# LED-DRIVER.net
KiCad netlist of a schematic drawn in Altium Designer
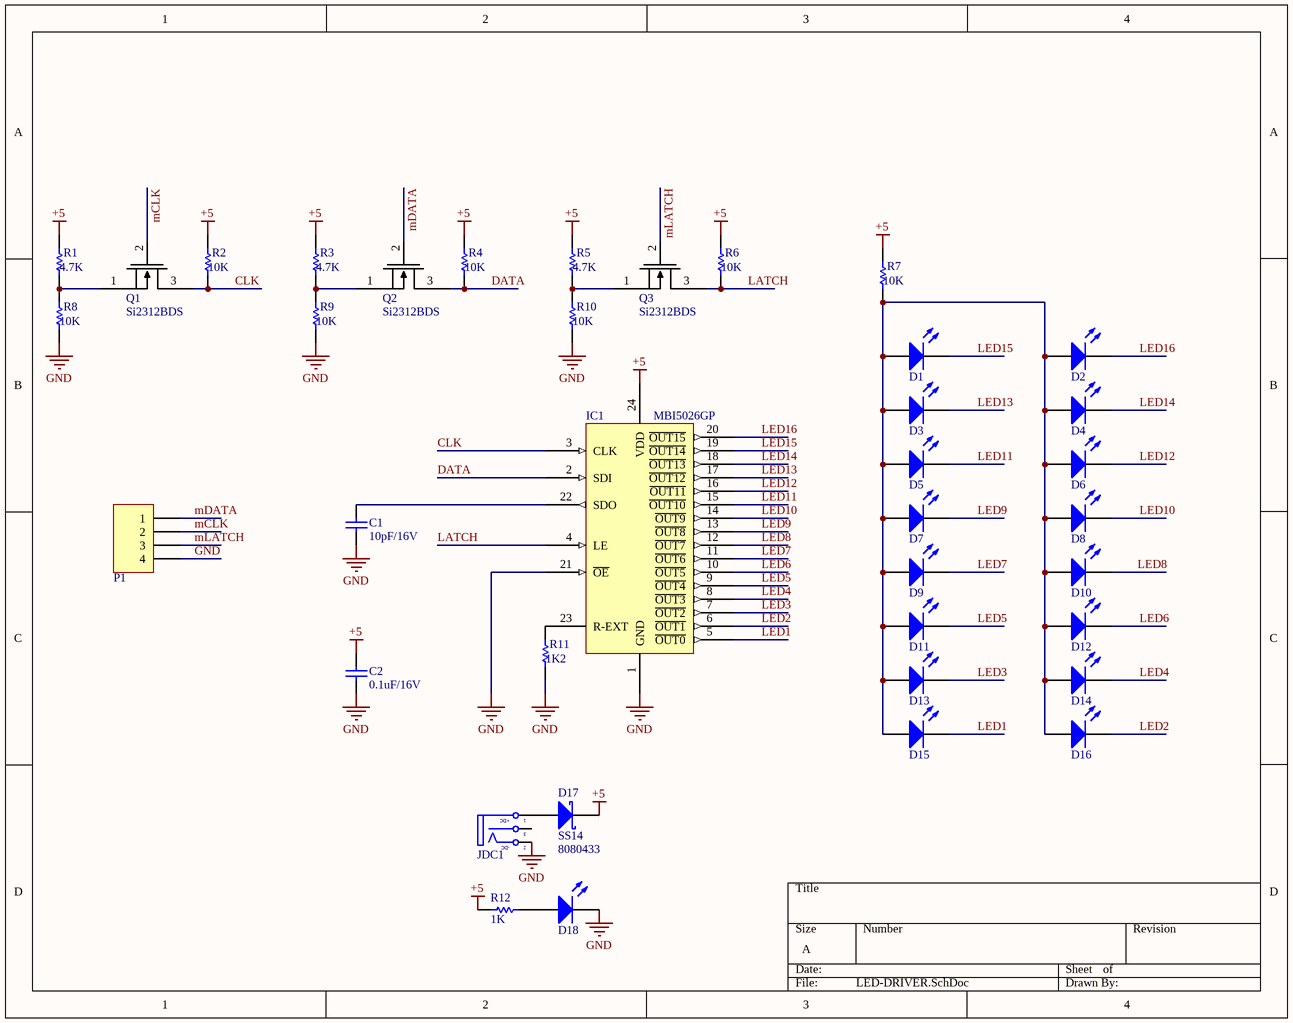
[diagram p0: LED-DRIVER.SchDoc]

(export (version "E")
  (design (tool "Eeschema 10.0.6"))
  (components
    (comp (ref "C1")
      (value "10pF/16V")
      (footprint "CAP-SM-0603")
      (description "Capacitor")
      (fields (field (name "Comment") "Cap Non-Pol SMD"))
      (libsource (lib "PIF_Library") (part "Cap Non-Pol SMD"))
    )
    (comp (ref "C2")
      (value "0.1uF/16V")
      (footprint "CAP-SM-0603")
      (description "Capacitor")
      (fields (field (name "Comment") "Cap Non-Pol SMD"))
      (libsource (lib "PIF_Library") (part "Cap Non-Pol SMD"))
    )
    (comp (ref "D1")
      (value "LED SMD")
      (footprint "LED_0603_Blue")
      (description "LED")
      (libsource (lib "PIF_Library") (part "LED SMD"))
    )
    (comp (ref "D2")
      (value "LED SMD")
      (footprint "LED_0603_Blue")
      (description "LED")
      (libsource (lib "PIF_Library") (part "LED SMD"))
    )
    (comp (ref "D3")
      (value "LED SMD")
      (footprint "LED_0603_Blue")
      (description "LED")
      (libsource (lib "PIF_Library") (part "LED SMD"))
    )
    (comp (ref "D4")
      (value "LED SMD")
      (footprint "LED_0603_Blue")
      (description "LED")
      (libsource (lib "PIF_Library") (part "LED SMD"))
    )
    (comp (ref "D5")
      (value "LED SMD")
      (footprint "LED_0603_Blue")
      (description "LED")
      (libsource (lib "PIF_Library") (part "LED SMD"))
    )
    (comp (ref "D6")
      (value "LED SMD")
      (footprint "LED_0603_Blue")
      (description "LED")
      (libsource (lib "PIF_Library") (part "LED SMD"))
    )
    (comp (ref "D7")
      (value "LED SMD")
      (footprint "LED_0603_Blue")
      (description "LED")
      (libsource (lib "PIF_Library") (part "LED SMD"))
    )
    (comp (ref "D8")
      (value "LED SMD")
      (footprint "LED_0603_Blue")
      (description "LED")
      (libsource (lib "PIF_Library") (part "LED SMD"))
    )
    (comp (ref "D9")
      (value "LED SMD")
      (footprint "LED_0603_Blue")
      (description "LED")
      (libsource (lib "PIF_Library") (part "LED SMD"))
    )
    (comp (ref "D10")
      (value "LED SMD")
      (footprint "LED_0603_Blue")
      (description "LED")
      (libsource (lib "PIF_Library") (part "LED SMD"))
    )
    (comp (ref "D11")
      (value "LED SMD")
      (footprint "LED_0603_Blue")
      (description "LED")
      (libsource (lib "PIF_Library") (part "LED SMD"))
    )
    (comp (ref "D12")
      (value "LED SMD")
      (footprint "LED_0603_Blue")
      (description "LED")
      (libsource (lib "PIF_Library") (part "LED SMD"))
    )
    (comp (ref "D13")
      (value "LED SMD")
      (footprint "LED_0603_Blue")
      (description "LED")
      (libsource (lib "PIF_Library") (part "LED SMD"))
    )
    (comp (ref "D14")
      (value "LED SMD")
      (footprint "LED_0603_Blue")
      (description "LED")
      (libsource (lib "PIF_Library") (part "LED SMD"))
    )
    (comp (ref "D15")
      (value "LED SMD")
      (footprint "LED_0603_Blue")
      (description "LED")
      (libsource (lib "PIF_Library") (part "LED SMD"))
    )
    (comp (ref "D16")
      (value "LED SMD")
      (footprint "LED_0603_Blue")
      (description "LED")
      (libsource (lib "PIF_Library") (part "LED SMD"))
    )
    (comp (ref "D17")
      (value "D Schottky")
      (footprint "SS34")
      (description "Schottky Diode")
      (fields
        (field (name "SUPPLIER PART NUMBER 1") "SS14")
        (field (name "SUPPLIER PART NUMBER 2") "8080433")
        (field (name "PUBLISHER") "Altium Limited")
      )
      (libsource (lib "PIF_Library") (part "D Schottky"))
    )
    (comp (ref "D18")
      (value "LED SMD")
      (footprint "LED_0603_Blue")
      (description "LED")
      (libsource (lib "PIF_Library") (part "LED SMD"))
    )
    (comp (ref "IC1")
      (value "MBI5026GP")
      (footprint "MBI5026GP")
      (description "16-bit Constant Current LED Sink Driver")
      (libsource (lib "Giang's Libs") (part "MBI5026GP"))
    )
    (comp (ref "JDC1")
      (value "Jack DC")
      (footprint "DC-IN")
      (description "Jack DC input")
      (libsource (lib "PIF_Library") (part "Jack DC"))
    )
    (comp (ref "P1")
      (value "Header 4")
      (footprint "JP4")
      (description "Header, 4-Pin")
      (fields (field (name "PUBLISHER") "Altium Limited"))
      (libsource (lib "PIF_Library") (part "Header 4"))
    )
    (comp (ref "Q1")
      (value "Si2312BDS")
      (footprint "SOT95P245X110-3N")
      (fields (field (name "MANUFACTURER") "Vishay Semiconductors"))
      (libsource (lib "MiclsLib") (part "Si2312BDS"))
    )
    (comp (ref "Q2")
      (value "Si2312BDS")
      (footprint "SOT95P245X110-3N")
      (fields (field (name "MANUFACTURER") "Vishay Semiconductors"))
      (libsource (lib "MiclsLib") (part "Si2312BDS"))
    )
    (comp (ref "Q3")
      (value "Si2312BDS")
      (footprint "SOT95P245X110-3N")
      (fields (field (name "MANUFACTURER") "Vishay Semiconductors"))
      (libsource (lib "MiclsLib") (part "Si2312BDS"))
    )
    (comp (ref "R1")
      (value "4.7K")
      (footprint "RES-SM-0603")
      (description "Resistor")
      (fields (field (name "Comment") "RESISTOR SMD"))
      (libsource (lib "PIF_Library") (part "RESISTOR SMD"))
    )
    (comp (ref "R2")
      (value "10K")
      (footprint "RES-SM-0603")
      (description "Resistor")
      (fields (field (name "Comment") "RESISTOR SMD"))
      (libsource (lib "PIF_Library") (part "RESISTOR SMD"))
    )
    (comp (ref "R3")
      (value "4.7K")
      (footprint "RES-SM-0603")
      (description "Resistor")
      (fields (field (name "Comment") "RESISTOR SMD"))
      (libsource (lib "PIF_Library") (part "RESISTOR SMD"))
    )
    (comp (ref "R4")
      (value "10K")
      (footprint "RES-SM-0603")
      (description "Resistor")
      (fields (field (name "Comment") "RESISTOR SMD"))
      (libsource (lib "PIF_Library") (part "RESISTOR SMD"))
    )
    (comp (ref "R5")
      (value "4.7K")
      (footprint "RES-SM-0603")
      (description "Resistor")
      (fields (field (name "Comment") "RESISTOR SMD"))
      (libsource (lib "PIF_Library") (part "RESISTOR SMD"))
    )
    (comp (ref "R6")
      (value "10K")
      (footprint "RES-SM-0603")
      (description "Resistor")
      (fields (field (name "Comment") "RESISTOR SMD"))
      (libsource (lib "PIF_Library") (part "RESISTOR SMD"))
    )
    (comp (ref "R7")
      (value "10K")
      (footprint "RES-SM-0603")
      (description "Resistor")
      (fields (field (name "Comment") "RESISTOR SMD"))
      (libsource (lib "PIF_Library") (part "RESISTOR SMD"))
    )
    (comp (ref "R8")
      (value "10K")
      (footprint "RES-SM-0603")
      (description "Resistor")
      (fields (field (name "Comment") "RESISTOR SMD"))
      (libsource (lib "PIF_Library") (part "RESISTOR SMD"))
    )
    (comp (ref "R9")
      (value "10K")
      (footprint "RES-SM-0603")
      (description "Resistor")
      (fields (field (name "Comment") "RESISTOR SMD"))
      (libsource (lib "PIF_Library") (part "RESISTOR SMD"))
    )
    (comp (ref "R10")
      (value "10K")
      (footprint "RES-SM-0603")
      (description "Resistor")
      (fields (field (name "Comment") "RESISTOR SMD"))
      (libsource (lib "PIF_Library") (part "RESISTOR SMD"))
    )
    (comp (ref "R11")
      (value "1K2")
      (footprint "RES-SM-0603")
      (description "Resistor")
      (fields (field (name "Comment") "RESISTOR SMD"))
      (libsource (lib "PIF_Library") (part "RESISTOR SMD"))
    )
    (comp (ref "R12")
      (value "1K")
      (footprint "RES-SM-0603")
      (description "Resistor")
      (fields (field (name "Comment") "RESISTOR SMD"))
      (libsource (lib "PIF_Library") (part "RESISTOR SMD"))
    )
  )
  (nets
    (net (code "1") (name "+5") (class "Default")
      (node (ref "C2") (pin "2") (pinfunction "2_2") (pintype "passive"))
      (node (ref "D17") (pin "K") (pinfunction "K_K") (pintype "passive"))
      (node (ref "IC1") (pin "24") (pinfunction "VDD_24") (pintype "power_in"))
      (node (ref "R1") (pin "2") (pinfunction "2_2") (pintype "passive"))
      (node (ref "R12") (pin "1") (pinfunction "1_1") (pintype "passive"))
      (node (ref "R2") (pin "2") (pinfunction "2_2") (pintype "passive"))
      (node (ref "R3") (pin "2") (pinfunction "2_2") (pintype "passive"))
      (node (ref "R4") (pin "2") (pinfunction "2_2") (pintype "passive"))
      (node (ref "R5") (pin "2") (pinfunction "2_2") (pintype "passive"))
      (node (ref "R6") (pin "2") (pinfunction "2_2") (pintype "passive"))
      (node (ref "R7") (pin "2") (pinfunction "2_2") (pintype "passive"))
    )
    (net (code "2") (name "/CLK") (class "Default")
      (node (ref "IC1") (pin "3") (pinfunction "CLK_3") (pintype "input"))
      (node (ref "Q1") (pin "3") (pinfunction "3_3") (pintype "passive"))
      (node (ref "R2") (pin "1") (pinfunction "1_1") (pintype "passive"))
    )
    (net (code "3") (name "/DATA") (class "Default")
      (node (ref "IC1") (pin "2") (pinfunction "SDI_2") (pintype "input"))
      (node (ref "Q2") (pin "3") (pinfunction "3_3") (pintype "passive"))
      (node (ref "R4") (pin "1") (pinfunction "1_1") (pintype "passive"))
    )
    (net (code "4") (name "/LATCH") (class "Default")
      (node (ref "IC1") (pin "4") (pinfunction "LE_4") (pintype "input"))
      (node (ref "Q3") (pin "3") (pinfunction "3_3") (pintype "passive"))
      (node (ref "R6") (pin "1") (pinfunction "1_1") (pintype "passive"))
    )
    (net (code "5") (name "/LED1") (class "Default")
      (node (ref "D15") (pin "2") (pinfunction "K_2") (pintype "passive"))
      (node (ref "IC1") (pin "5") (pinfunction "~{OUT0}_5") (pintype "output"))
    )
    (net (code "6") (name "/LED2") (class "Default")
      (node (ref "D16") (pin "2") (pinfunction "K_2") (pintype "passive"))
      (node (ref "IC1") (pin "6") (pinfunction "~{OUT1}_6") (pintype "output"))
    )
    (net (code "7") (name "/LED3") (class "Default")
      (node (ref "D13") (pin "2") (pinfunction "K_2") (pintype "passive"))
      (node (ref "IC1") (pin "7") (pinfunction "~{OUT2}_7") (pintype "output"))
    )
    (net (code "8") (name "/LED4") (class "Default")
      (node (ref "D14") (pin "2") (pinfunction "K_2") (pintype "passive"))
      (node (ref "IC1") (pin "8") (pinfunction "~{OUT3}_8") (pintype "output"))
    )
    (net (code "9") (name "/LED5") (class "Default")
      (node (ref "D11") (pin "2") (pinfunction "K_2") (pintype "passive"))
      (node (ref "IC1") (pin "9") (pinfunction "~{OUT4}_9") (pintype "output"))
    )
    (net (code "10") (name "/LED6") (class "Default")
      (node (ref "D12") (pin "2") (pinfunction "K_2") (pintype "passive"))
      (node (ref "IC1") (pin "10") (pinfunction "~{OUT5}_10") (pintype "output"))
    )
    (net (code "11") (name "/LED7") (class "Default")
      (node (ref "D9") (pin "2") (pinfunction "K_2") (pintype "passive"))
      (node (ref "IC1") (pin "11") (pinfunction "~{OUT6}_11") (pintype "output"))
    )
    (net (code "12") (name "/LED8") (class "Default")
      (node (ref "D10") (pin "2") (pinfunction "K_2") (pintype "passive"))
      (node (ref "IC1") (pin "12") (pinfunction "~{OUT7}_12") (pintype "output"))
    )
    (net (code "13") (name "/LED9") (class "Default")
      (node (ref "D7") (pin "2") (pinfunction "K_2") (pintype "passive"))
      (node (ref "IC1") (pin "13") (pinfunction "~{OUT8}_13") (pintype "output"))
    )
    (net (code "14") (name "/LED10") (class "Default")
      (node (ref "D8") (pin "2") (pinfunction "K_2") (pintype "passive"))
      (node (ref "IC1") (pin "14") (pinfunction "~{OUT9}_14") (pintype "output"))
    )
    (net (code "15") (name "/LED11") (class "Default")
      (node (ref "D5") (pin "2") (pinfunction "K_2") (pintype "passive"))
      (node (ref "IC1") (pin "15") (pinfunction "~{OUT10}_15") (pintype "output"))
    )
    (net (code "16") (name "/LED12") (class "Default")
      (node (ref "D6") (pin "2") (pinfunction "K_2") (pintype "passive"))
      (node (ref "IC1") (pin "16") (pinfunction "~{OUT11}_16") (pintype "output"))
    )
    (net (code "17") (name "/LED13") (class "Default")
      (node (ref "D3") (pin "2") (pinfunction "K_2") (pintype "passive"))
      (node (ref "IC1") (pin "17") (pinfunction "~{OUT12}_17") (pintype "output"))
    )
    (net (code "18") (name "/LED14") (class "Default")
      (node (ref "D4") (pin "2") (pinfunction "K_2") (pintype "passive"))
      (node (ref "IC1") (pin "18") (pinfunction "~{OUT13}_18") (pintype "output"))
    )
    (net (code "19") (name "/LED15") (class "Default")
      (node (ref "D1") (pin "2") (pinfunction "K_2") (pintype "passive"))
      (node (ref "IC1") (pin "19") (pinfunction "~{OUT14}_19") (pintype "output"))
    )
    (net (code "20") (name "/LED16") (class "Default")
      (node (ref "D2") (pin "2") (pinfunction "K_2") (pintype "passive"))
      (node (ref "IC1") (pin "20") (pinfunction "~{OUT15}_20") (pintype "output"))
    )
    (net (code "21") (name "/mCLK") (class "Default")
      (node (ref "P1") (pin "2") (pinfunction "2_2") (pintype "passive"))
      (node (ref "Q1") (pin "2") (pinfunction "2_2") (pintype "passive"))
    )
    (net (code "22") (name "/mDATA") (class "Default")
      (node (ref "P1") (pin "1") (pinfunction "1_1") (pintype "passive"))
      (node (ref "Q2") (pin "2") (pinfunction "2_2") (pintype "passive"))
    )
    (net (code "23") (name "/mLATCH") (class "Default")
      (node (ref "P1") (pin "3") (pinfunction "3_3") (pintype "passive"))
      (node (ref "Q3") (pin "2") (pinfunction "2_2") (pintype "passive"))
    )
    (net (code "24") (name "GND") (class "Default")
      (node (ref "C1") (pin "1") (pinfunction "1_1") (pintype "passive"))
      (node (ref "C2") (pin "1") (pinfunction "1_1") (pintype "passive"))
      (node (ref "D18") (pin "2") (pinfunction "K_2") (pintype "passive"))
      (node (ref "IC1") (pin "1") (pinfunction "GND_1") (pintype "passive"))
      (node (ref "IC1") (pin "21") (pinfunction "~{OE}_21") (pintype "input"))
      (node (ref "JDC1") (pin "2") (pinfunction "TN_2") (pintype "passive"))
      (node (ref "P1") (pin "4") (pinfunction "4_4") (pintype "passive"))
      (node (ref "R10") (pin "1") (pinfunction "1_1") (pintype "passive"))
      (node (ref "R11") (pin "1") (pinfunction "1_1") (pintype "passive"))
      (node (ref "R8") (pin "1") (pinfunction "1_1") (pintype "passive"))
      (node (ref "R9") (pin "1") (pinfunction "1_1") (pintype "passive"))
    )
    (net (code "25") (name "Net-(D1-A)") (class "Default")
      (node (ref "D1") (pin "1") (pinfunction "A_1") (pintype "passive"))
      (node (ref "D10") (pin "1") (pinfunction "A_1") (pintype "passive"))
      (node (ref "D11") (pin "1") (pinfunction "A_1") (pintype "passive"))
      (node (ref "D12") (pin "1") (pinfunction "A_1") (pintype "passive"))
      (node (ref "D13") (pin "1") (pinfunction "A_1") (pintype "passive"))
      (node (ref "D14") (pin "1") (pinfunction "A_1") (pintype "passive"))
      (node (ref "D15") (pin "1") (pinfunction "A_1") (pintype "passive"))
      (node (ref "D16") (pin "1") (pinfunction "A_1") (pintype "passive"))
      (node (ref "D2") (pin "1") (pinfunction "A_1") (pintype "passive"))
      (node (ref "D3") (pin "1") (pinfunction "A_1") (pintype "passive"))
      (node (ref "D4") (pin "1") (pinfunction "A_1") (pintype "passive"))
      (node (ref "D5") (pin "1") (pinfunction "A_1") (pintype "passive"))
      (node (ref "D6") (pin "1") (pinfunction "A_1") (pintype "passive"))
      (node (ref "D7") (pin "1") (pinfunction "A_1") (pintype "passive"))
      (node (ref "D8") (pin "1") (pinfunction "A_1") (pintype "passive"))
      (node (ref "D9") (pin "1") (pinfunction "A_1") (pintype "passive"))
      (node (ref "R7") (pin "1") (pinfunction "1_1") (pintype "passive"))
    )
    (net (code "26") (name "Net-(D18-A)") (class "Default")
      (node (ref "D18") (pin "1") (pinfunction "A_1") (pintype "passive"))
      (node (ref "R12") (pin "2") (pinfunction "2_2") (pintype "passive"))
    )
    (net (code "27") (name "Net-(IC1-R-EXT)") (class "Default")
      (node (ref "IC1") (pin "23") (pinfunction "R-EXT_23") (pintype "passive"))
      (node (ref "R11") (pin "2") (pinfunction "2_2") (pintype "passive"))
    )
    (net (code "28") (name "Net-(IC1-SDO)") (class "Default")
      (node (ref "C1") (pin "2") (pinfunction "2_2") (pintype "passive"))
      (node (ref "IC1") (pin "22") (pinfunction "SDO_22") (pintype "output"))
    )
    (net (code "29") (name "Net-(JDC1-T)") (class "Default")
      (node (ref "D17") (pin "A") (pinfunction "A_A") (pintype "passive"))
      (node (ref "JDC1") (pin "1") (pinfunction "T_1") (pintype "passive"))
    )
    (net (code "30") (name "Net-(Q1-Pad1)") (class "Default")
      (node (ref "Q1") (pin "1") (pinfunction "1_1") (pintype "passive"))
      (node (ref "R1") (pin "1") (pinfunction "1_1") (pintype "passive"))
      (node (ref "R8") (pin "2") (pinfunction "2_2") (pintype "passive"))
    )
    (net (code "31") (name "Net-(Q2-Pad1)") (class "Default")
      (node (ref "Q2") (pin "1") (pinfunction "1_1") (pintype "passive"))
      (node (ref "R3") (pin "1") (pinfunction "1_1") (pintype "passive"))
      (node (ref "R9") (pin "2") (pinfunction "2_2") (pintype "passive"))
    )
    (net (code "32") (name "Net-(Q3-Pad1)") (class "Default")
      (node (ref "Q3") (pin "1") (pinfunction "1_1") (pintype "passive"))
      (node (ref "R10") (pin "2") (pinfunction "2_2") (pintype "passive"))
      (node (ref "R5") (pin "1") (pinfunction "1_1") (pintype "passive"))
    )
    (net (code "33") (name "unconnected-(JDC1-S-Pad3)") (class "Default")
      (node (ref "JDC1") (pin "3") (pinfunction "S_3") (pintype "power_in"))
    )
  )
)
